# MINI.net
KiCad netlist of a schematic drawn in EAGLE
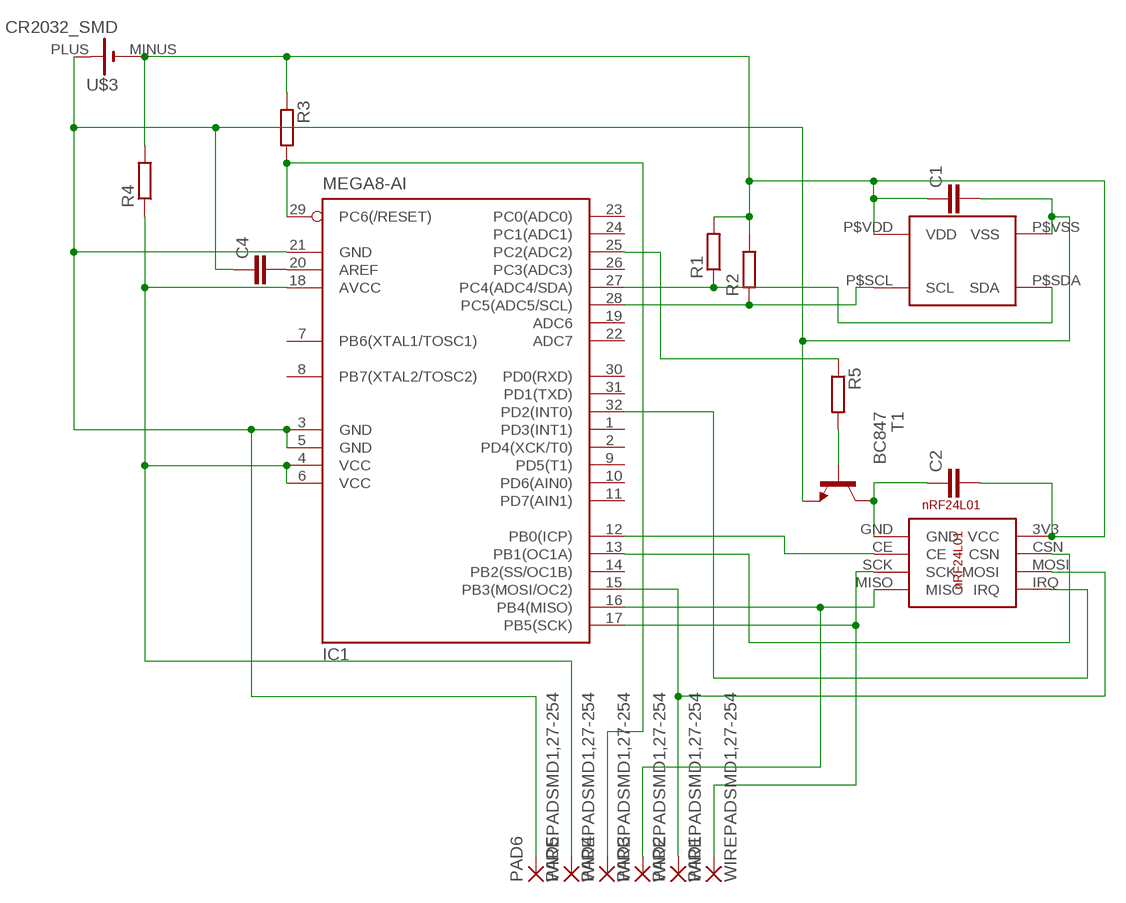
[diagram p0: schematic, sheet 1]

(export (version "E")
  (design (tool "Eeschema 10.0.6"))
  (components
    (comp (ref "C1")
      (value "C-EUC0805K")
      (footprint "eagle-import:C0805K")
      (libsource (lib "eagle-import") (part "C-EUC0805K"))
    )
    (comp (ref "C2")
      (value "C-EUC0805")
      (footprint "eagle-import:C0805")
      (libsource (lib "eagle-import") (part "C-EUC0805"))
    )
    (comp (ref "C4")
      (value "C-EUC0805")
      (footprint "eagle-import:C0805")
      (libsource (lib "eagle-import") (part "C-EUC0805"))
    )
    (comp (ref "IC1")
      (value "MEGA8-AI")
      (footprint "eagle-import:TQFP32-08")
      (fields (field (name "MPN") "ATMEGA8-16AU"))
      (libsource (lib "eagle-import") (part "MEGA8-AI"))
    )
    (comp (ref "MINI1")
      (value "NRF24L01BMINI")
      (footprint "eagle-import:MINI")
      (libsource (lib "eagle-import") (part "NRF24L01BMINI"))
    )
    (comp (ref "PAD1")
      (value "WIREPADSMD1,27-254")
      (footprint "eagle-import:SMD1,27-2,54")
      (libsource (lib "eagle-import") (part "WIREPADSMD1,27-254"))
    )
    (comp (ref "PAD2")
      (value "WIREPADSMD1,27-254")
      (footprint "eagle-import:SMD1,27-2,54")
      (libsource (lib "eagle-import") (part "WIREPADSMD1,27-254"))
    )
    (comp (ref "PAD3")
      (value "WIREPADSMD1,27-254")
      (footprint "eagle-import:SMD1,27-2,54")
      (libsource (lib "eagle-import") (part "WIREPADSMD1,27-254"))
    )
    (comp (ref "PAD4")
      (value "WIREPADSMD1,27-254")
      (footprint "eagle-import:SMD1,27-2,54")
      (libsource (lib "eagle-import") (part "WIREPADSMD1,27-254"))
    )
    (comp (ref "PAD5")
      (value "WIREPADSMD1,27-254")
      (footprint "eagle-import:SMD1,27-2,54")
      (libsource (lib "eagle-import") (part "WIREPADSMD1,27-254"))
    )
    (comp (ref "PAD6")
      (value "WIREPADSMD1,27-254")
      (footprint "eagle-import:SMD1,27-2,54")
      (libsource (lib "eagle-import") (part "WIREPADSMD1,27-254"))
    )
    (comp (ref "R1")
      (value "R-EU_R1206W")
      (footprint "eagle-import:R1206W")
      (libsource (lib "eagle-import") (part "R-EU_R1206W"))
    )
    (comp (ref "R2")
      (value "R-EU_R1206W")
      (footprint "eagle-import:R1206W")
      (libsource (lib "eagle-import") (part "R-EU_R1206W"))
    )
    (comp (ref "R3")
      (value "R-EU_R0805")
      (footprint "eagle-import:R0805")
      (libsource (lib "eagle-import") (part "R-EU_R0805"))
    )
    (comp (ref "R4")
      (value "R-EU_R1206")
      (footprint "eagle-import:R1206")
      (libsource (lib "eagle-import") (part "R-EU_R1206"))
    )
    (comp (ref "R5")
      (value "R-EU_R0805W")
      (footprint "eagle-import:R0805W")
      (libsource (lib "eagle-import") (part "R-EU_R0805W"))
    )
    (comp (ref "T1")
      (value "BC847")
      (footprint "eagle-import:SOT23")
      (libsource (lib "eagle-import") (part "BC847"))
    )
    (comp (ref "U$1")
      (value "SHT21")
      (footprint "eagle-import:DFN6")
      (libsource (lib "eagle-import") (part "SHT21"))
    )
    (comp (ref "U$3")
      (value "CR2032_SMD")
      (footprint "eagle-import:CR2032_SMD")
      (libsource (lib "eagle-import") (part "CR2032_SMD"))
    )
  )
  (nets
    (net (code "1") (name "Net-(IC1-AREF)") (class "Default")
      (node (ref "C4") (pin "2") (pinfunction "2_2") (pintype "passive"))
      (node (ref "IC1") (pin "20") (pinfunction "AREF_20") (pintype "passive"))
    )
    (net (code "2") (name "Net-(IC1-AVCC)") (class "Default")
      (node (ref "IC1") (pin "18") (pinfunction "AVCC_18") (pintype "power_in"))
      (node (ref "IC1") (pin "4") (pinfunction "VCC_4") (pintype "power_in"))
      (node (ref "IC1") (pin "6") (pinfunction "VCC_6") (pintype "power_in"))
      (node (ref "PAD5") (pin "1") (pinfunction "P_1") (pintype "passive"))
      (node (ref "R4") (pin "1") (pinfunction "1_1") (pintype "passive"))
    )
    (net (code "3") (name "Net-(IC1-PB0(ICP))") (class "Default")
      (node (ref "IC1") (pin "12") (pinfunction "PB0(ICP)_12") (pintype "bidirectional"))
      (node (ref "MINI1") (pin "CE") (pinfunction "CE_CE") (pintype "bidirectional"))
    )
    (net (code "4") (name "Net-(IC1-PB1(OC1A))") (class "Default")
      (node (ref "IC1") (pin "13") (pinfunction "PB1(OC1A)_13") (pintype "bidirectional"))
      (node (ref "MINI1") (pin "CSN") (pinfunction "CSN_CSN") (pintype "bidirectional"))
    )
    (net (code "5") (name "Net-(IC1-PB3(MOSI{slash}OC2))") (class "Default")
      (node (ref "IC1") (pin "15") (pinfunction "PB3(MOSI/OC2)_15") (pintype "bidirectional"))
      (node (ref "MINI1") (pin "MOSI") (pinfunction "MOSI_MOSI") (pintype "bidirectional"))
      (node (ref "PAD2") (pin "1") (pinfunction "P_1") (pintype "passive"))
    )
    (net (code "6") (name "Net-(IC1-PB4(MISO))") (class "Default")
      (node (ref "IC1") (pin "16") (pinfunction "PB4(MISO)_16") (pintype "bidirectional"))
      (node (ref "MINI1") (pin "MISO") (pinfunction "MISO_MISO") (pintype "bidirectional"))
      (node (ref "PAD3") (pin "1") (pinfunction "P_1") (pintype "passive"))
    )
    (net (code "7") (name "Net-(IC1-PB5(SCK))") (class "Default")
      (node (ref "IC1") (pin "17") (pinfunction "PB5(SCK)_17") (pintype "bidirectional"))
      (node (ref "MINI1") (pin "SCK") (pinfunction "SCK_SCK") (pintype "bidirectional"))
      (node (ref "PAD1") (pin "1") (pinfunction "P_1") (pintype "passive"))
    )
    (net (code "8") (name "Net-(IC1-PC2(ADC2))") (class "Default")
      (node (ref "IC1") (pin "25") (pinfunction "PC2(ADC2)_25") (pintype "bidirectional"))
      (node (ref "R5") (pin "1") (pinfunction "1_1") (pintype "passive"))
    )
    (net (code "9") (name "Net-(IC1-PC4(ADC4{slash}SDA))") (class "Default")
      (node (ref "IC1") (pin "27") (pinfunction "PC4(ADC4/SDA)_27") (pintype "bidirectional"))
      (node (ref "R1") (pin "1") (pinfunction "1_1") (pintype "passive"))
      (node (ref "U$1") (pin "P$SDA") (pinfunction "SDA_P$SDA") (pintype "bidirectional"))
    )
    (net (code "10") (name "Net-(IC1-PC5(ADC5{slash}SCL))") (class "Default")
      (node (ref "IC1") (pin "28") (pinfunction "PC5(ADC5/SCL)_28") (pintype "bidirectional"))
      (node (ref "R2") (pin "1") (pinfunction "1_1") (pintype "passive"))
      (node (ref "U$1") (pin "P$SCL") (pinfunction "SCL_P$SCL") (pintype "bidirectional"))
    )
    (net (code "11") (name "Net-(IC1-PC6({slash}RESET))") (class "Default")
      (node (ref "IC1") (pin "29") (pinfunction "PC6(/RESET)_29") (pintype "bidirectional"))
      (node (ref "PAD4") (pin "1") (pinfunction "P_1") (pintype "passive"))
      (node (ref "R3") (pin "2") (pinfunction "2_2") (pintype "passive"))
    )
    (net (code "12") (name "Net-(IC1-PD2(INT0))") (class "Default")
      (node (ref "IC1") (pin "32") (pinfunction "PD2(INT0)_32") (pintype "bidirectional"))
      (node (ref "MINI1") (pin "IRQ") (pinfunction "IRQ_IRQ") (pintype "bidirectional"))
    )
    (net (code "13") (name "Net-(MINI1-VCC)") (class "Default")
      (node (ref "C1") (pin "1") (pinfunction "1_1") (pintype "passive"))
      (node (ref "C2") (pin "2") (pinfunction "2_2") (pintype "passive"))
      (node (ref "MINI1") (pin "3V3") (pinfunction "VCC_3V3") (pintype "bidirectional"))
      (node (ref "R1") (pin "2") (pinfunction "2_2") (pintype "passive"))
      (node (ref "R2") (pin "2") (pinfunction "2_2") (pintype "passive"))
      (node (ref "R3") (pin "1") (pinfunction "1_1") (pintype "passive"))
      (node (ref "R4") (pin "2") (pinfunction "2_2") (pintype "passive"))
      (node (ref "U$1") (pin "P$VDD") (pinfunction "VDD_P$VDD") (pintype "bidirectional"))
      (node (ref "U$3") (pin "MINUS") (pinfunction "-_MINUS") (pintype "passive"))
    )
    (net (code "14") (name "Net-(PAD6-P)") (class "Default")
      (node (ref "C1") (pin "2") (pinfunction "2_2") (pintype "passive"))
      (node (ref "C4") (pin "1") (pinfunction "1_1") (pintype "passive"))
      (node (ref "IC1") (pin "21") (pinfunction "GND_21") (pintype "power_in"))
      (node (ref "IC1") (pin "3") (pinfunction "GND_3") (pintype "power_in"))
      (node (ref "IC1") (pin "5") (pinfunction "GND_5") (pintype "power_in"))
      (node (ref "PAD6") (pin "1") (pinfunction "P_1") (pintype "passive"))
      (node (ref "T1") (pin "2") (pinfunction "E_2") (pintype "passive"))
      (node (ref "U$1") (pin "P$VSS") (pinfunction "VSS_P$VSS") (pintype "bidirectional"))
      (node (ref "U$3") (pin "PLUS") (pinfunction "+_PLUS") (pintype "passive"))
    )
    (net (code "15") (name "Net-(T1-B)") (class "Default")
      (node (ref "R5") (pin "2") (pinfunction "2_2") (pintype "passive"))
      (node (ref "T1") (pin "1") (pinfunction "B_1") (pintype "passive"))
    )
    (net (code "16") (name "Net-(T1-C)") (class "Default")
      (node (ref "C2") (pin "1") (pinfunction "1_1") (pintype "passive"))
      (node (ref "MINI1") (pin "GND") (pinfunction "GND_GND") (pintype "bidirectional"))
      (node (ref "T1") (pin "3") (pinfunction "C_3") (pintype "passive"))
    )
    (net (code "17") (name "unconnected-(IC1-ADC6-Pad19)") (class "Default")
      (node (ref "IC1") (pin "19") (pinfunction "ADC6_19") (pintype "bidirectional"))
    )
    (net (code "18") (name "unconnected-(IC1-ADC7-Pad22)") (class "Default")
      (node (ref "IC1") (pin "22") (pinfunction "ADC7_22") (pintype "bidirectional"))
    )
    (net (code "19") (name "unconnected-(IC1-PB2(SS{slash}OC1B)-Pad14)") (class "Default")
      (node (ref "IC1") (pin "14") (pinfunction "PB2(SS/OC1B)_14") (pintype "bidirectional"))
    )
    (net (code "20") (name "unconnected-(IC1-PB6(XTAL1{slash}TOSC1)-Pad7)") (class "Default")
      (node (ref "IC1") (pin "7") (pinfunction "PB6(XTAL1/TOSC1)_7") (pintype "bidirectional"))
    )
    (net (code "21") (name "unconnected-(IC1-PB7(XTAL2{slash}TOSC2)-Pad8)") (class "Default")
      (node (ref "IC1") (pin "8") (pinfunction "PB7(XTAL2/TOSC2)_8") (pintype "bidirectional"))
    )
    (net (code "22") (name "unconnected-(IC1-PC0(ADC0)-Pad23)") (class "Default")
      (node (ref "IC1") (pin "23") (pinfunction "PC0(ADC0)_23") (pintype "bidirectional"))
    )
    (net (code "23") (name "unconnected-(IC1-PC1(ADC1)-Pad24)") (class "Default")
      (node (ref "IC1") (pin "24") (pinfunction "PC1(ADC1)_24") (pintype "bidirectional"))
    )
    (net (code "24") (name "unconnected-(IC1-PC3(ADC3)-Pad26)") (class "Default")
      (node (ref "IC1") (pin "26") (pinfunction "PC3(ADC3)_26") (pintype "bidirectional"))
    )
    (net (code "25") (name "unconnected-(IC1-PD0(RXD)-Pad30)") (class "Default")
      (node (ref "IC1") (pin "30") (pinfunction "PD0(RXD)_30") (pintype "bidirectional"))
    )
    (net (code "26") (name "unconnected-(IC1-PD1(TXD)-Pad31)") (class "Default")
      (node (ref "IC1") (pin "31") (pinfunction "PD1(TXD)_31") (pintype "bidirectional"))
    )
    (net (code "27") (name "unconnected-(IC1-PD3(INT1)-Pad1)") (class "Default")
      (node (ref "IC1") (pin "1") (pinfunction "PD3(INT1)_1") (pintype "bidirectional"))
    )
    (net (code "28") (name "unconnected-(IC1-PD4(XCK{slash}T0)-Pad2)") (class "Default")
      (node (ref "IC1") (pin "2") (pinfunction "PD4(XCK/T0)_2") (pintype "bidirectional"))
    )
    (net (code "29") (name "unconnected-(IC1-PD5(T1)-Pad9)") (class "Default")
      (node (ref "IC1") (pin "9") (pinfunction "PD5(T1)_9") (pintype "bidirectional"))
    )
    (net (code "30") (name "unconnected-(IC1-PD6(AIN0)-Pad10)") (class "Default")
      (node (ref "IC1") (pin "10") (pinfunction "PD6(AIN0)_10") (pintype "bidirectional"))
    )
    (net (code "31") (name "unconnected-(IC1-PD7(AIN1)-Pad11)") (class "Default")
      (node (ref "IC1") (pin "11") (pinfunction "PD7(AIN1)_11") (pintype "bidirectional"))
    )
  )
)
